# IMX219_Bridge.net
KiCad netlist of a schematic drawn in Altium Designer
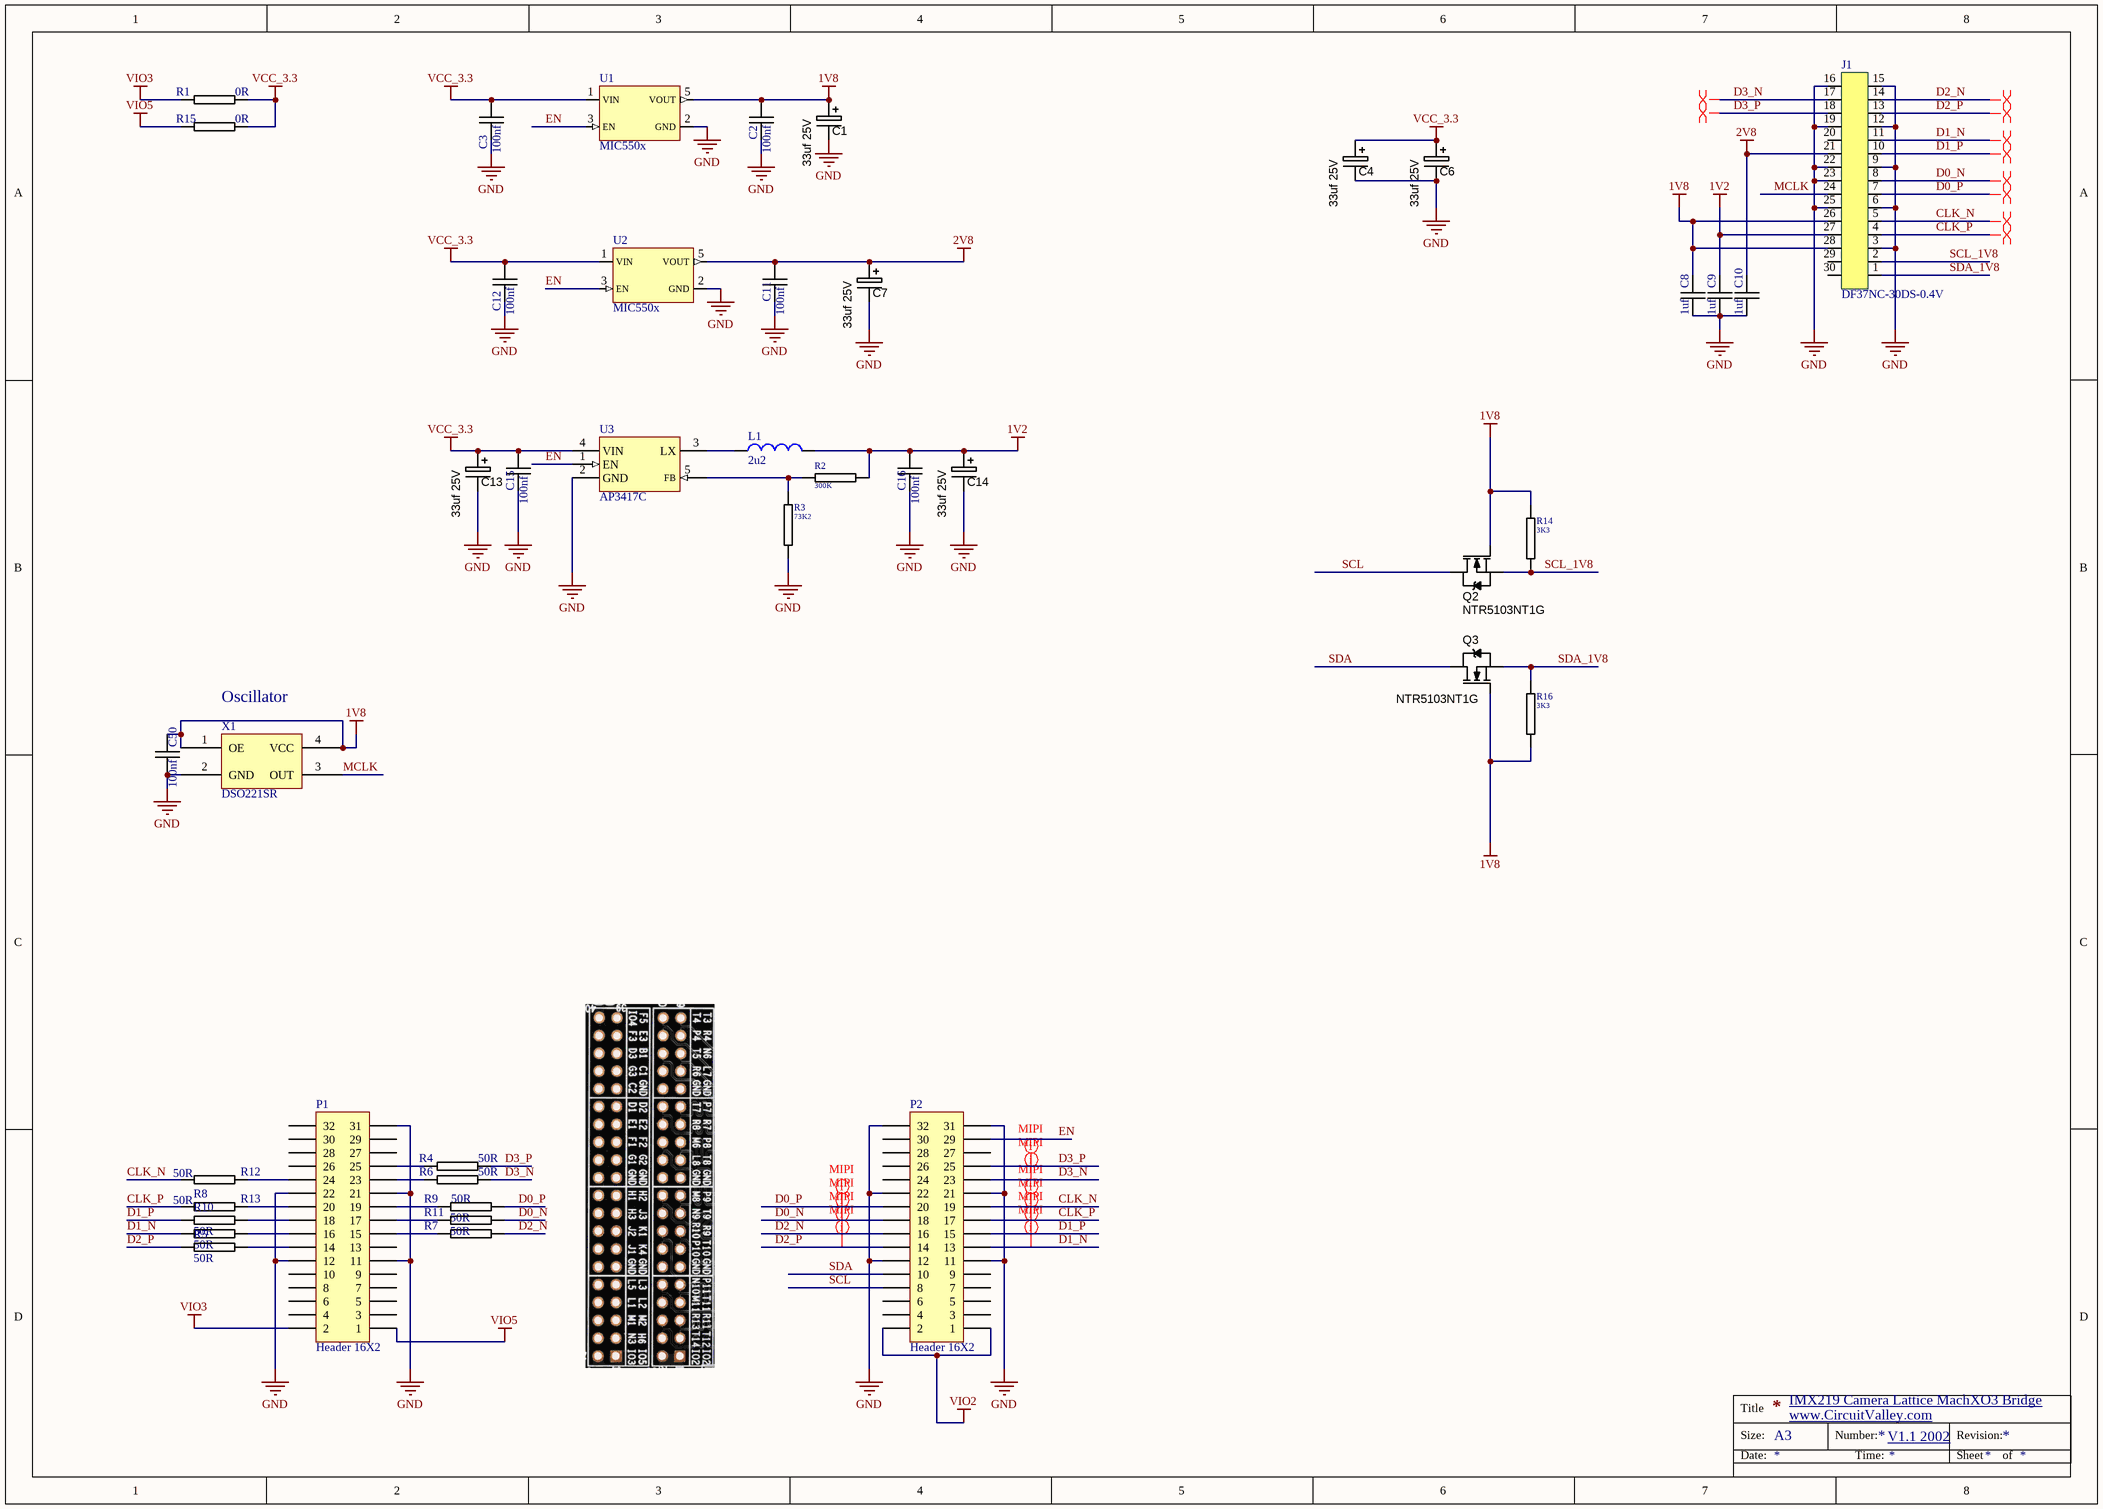
[diagram p0: IMX219_Bridge.SchDoc]

(export (version "E")
  (design (tool "Eeschema 10.0.6"))
  (components
    (comp (ref "C1")
      (value "33uf 25V")
      (footprint "CAPMP7343X310N")
      (description "Capacitor SMD Tant 330uF 20% 6V3 2917")
      (fields
        (field (name "TOLERANCE") "±20%")
        (field (name "MANUFACTURER PART NUMBER") "T520D337M006ATE015")
      )
      (libsource (lib "PBL - Capacitors") (part "CAPT_330u_2917_6V3"))
    )
    (comp (ref "C2")
      (value "100nf")
      (footprint "0603C-GENERIC")
      (description "CAPACITOR 0603 CERAMIC")
      (fields
        (field (name "MANUFACTURER") "Murata Electronics North America")
        (field (name "MANUFACTURER PART NUMBER") "GRM188R60J106ME47D")
      )
      (libsource (lib "Generic") (part "0603C-10UF-6V3-X5R-MUR"))
    )
    (comp (ref "C3")
      (value "100nf")
      (footprint "0603C-GENERIC")
      (description "CAPACITOR 0603 CERAMIC")
      (fields
        (field (name "MANUFACTURER") "Murata Electronics North America")
        (field (name "MANUFACTURER PART NUMBER") "GRM188R60J106ME47D")
      )
      (libsource (lib "Generic") (part "0603C-10UF-6V3-X5R-MUR"))
    )
    (comp (ref "C4")
      (value "33uf 25V")
      (footprint "CAPMP7343X310N")
      (description "Capacitor SMD Tant 330uF 20% 6V3 2917")
      (fields
        (field (name "TOLERANCE") "±20%")
        (field (name "MANUFACTURER PART NUMBER") "T520D337M006ATE015")
      )
      (libsource (lib "PBL - Capacitors") (part "CAPT_330u_2917_6V3"))
    )
    (comp (ref "C6")
      (value "33uf 25V")
      (footprint "CAPMP7343X310N")
      (description "Capacitor SMD Tant 330uF 20% 6V3 2917")
      (fields
        (field (name "TOLERANCE") "±20%")
        (field (name "MANUFACTURER PART NUMBER") "T520D337M006ATE015")
      )
      (libsource (lib "PBL - Capacitors") (part "CAPT_330u_2917_6V3"))
    )
    (comp (ref "C7")
      (value "33uf 25V")
      (footprint "CAPMP7343X310N")
      (description "Capacitor SMD Tant 330uF 20% 6V3 2917")
      (fields
        (field (name "TOLERANCE") "±20%")
        (field (name "MANUFACTURER PART NUMBER") "T520D337M006ATE015")
      )
      (libsource (lib "PBL - Capacitors") (part "CAPT_330u_2917_6V3"))
    )
    (comp (ref "C8")
      (value "1uf")
      (footprint "0805C-TBD")
      (description "CAPACITOR 0805 CERAMIC VALUE TO BE DETERMINED")
      (libsource (lib "Generic") (part "0805C-TBD"))
    )
    (comp (ref "C9")
      (value "1uf")
      (footprint "0805C-TBD")
      (description "CAPACITOR 0805 CERAMIC VALUE TO BE DETERMINED")
      (libsource (lib "Generic") (part "0805C-TBD"))
    )
    (comp (ref "C10")
      (value "1uf")
      (footprint "0805C-TBD")
      (description "CAPACITOR 0805 CERAMIC VALUE TO BE DETERMINED")
      (libsource (lib "Generic") (part "0805C-TBD"))
    )
    (comp (ref "C11")
      (value "100nf")
      (footprint "0603C-GENERIC")
      (description "CAPACITOR 0603 CERAMIC")
      (fields
        (field (name "MANUFACTURER") "Murata Electronics North America")
        (field (name "MANUFACTURER PART NUMBER") "GRM188R60J106ME47D")
      )
      (libsource (lib "Generic") (part "0603C-10UF-6V3-X5R-MUR"))
    )
    (comp (ref "C12")
      (value "100nf")
      (footprint "0603C-GENERIC")
      (description "CAPACITOR 0603 CERAMIC")
      (fields
        (field (name "MANUFACTURER") "Murata Electronics North America")
        (field (name "MANUFACTURER PART NUMBER") "GRM188R60J106ME47D")
      )
      (libsource (lib "Generic") (part "0603C-10UF-6V3-X5R-MUR"))
    )
    (comp (ref "C13")
      (value "33uf 25V")
      (footprint "CAPMP7343X310N")
      (description "Capacitor SMD Tant 330uF 20% 6V3 2917")
      (fields
        (field (name "TOLERANCE") "±20%")
        (field (name "MANUFACTURER PART NUMBER") "T520D337M006ATE015")
      )
      (libsource (lib "PBL - Capacitors") (part "CAPT_330u_2917_6V3"))
    )
    (comp (ref "C14")
      (value "33uf 25V")
      (footprint "CAPMP7343X310N")
      (description "Capacitor SMD Tant 330uF 20% 6V3 2917")
      (fields
        (field (name "TOLERANCE") "±20%")
        (field (name "MANUFACTURER PART NUMBER") "T520D337M006ATE015")
      )
      (libsource (lib "PBL - Capacitors") (part "CAPT_330u_2917_6V3"))
    )
    (comp (ref "C15")
      (value "100nf")
      (footprint "0603C-GENERIC")
      (description "CAPACITOR 0603 CERAMIC")
      (fields
        (field (name "MANUFACTURER") "Murata Electronics North America")
        (field (name "MANUFACTURER PART NUMBER") "GRM188R60J106ME47D")
      )
      (libsource (lib "Generic") (part "0603C-10UF-6V3-X5R-MUR"))
    )
    (comp (ref "C16")
      (value "100nf")
      (footprint "0603C-GENERIC")
      (description "CAPACITOR 0603 CERAMIC")
      (fields
        (field (name "MANUFACTURER") "Murata Electronics North America")
        (field (name "MANUFACTURER PART NUMBER") "GRM188R60J106ME47D")
      )
      (libsource (lib "Generic") (part "0603C-10UF-6V3-X5R-MUR"))
    )
    (comp (ref "C50")
      (value "100nf")
      (footprint "0603C-GENERIC")
      (description "CAPACITOR 0603 CERAMIC")
      (fields
        (field (name "MANUFACTURER") "Murata Electronics North America")
        (field (name "MANUFACTURER PART NUMBER") "GRM188R60J106ME47D")
      )
      (libsource (lib "Generic") (part "0603C-10UF-6V3-X5R-MUR"))
    )
    (comp (ref "J1")
      (value "DF37NC-30DS-0.4V")
      (footprint "DF37NC-30DS-0.4V")
      (libsource (lib "Hiros") (part "30_Pin_Dual"))
    )
    (comp (ref "L1")
      (value "2u2")
      (footprint "TAIYO_NRS4018T2R2MDGJ")
      (fields (field (name "PARTNUMBER") "NRS4018T2R2MDGJ"))
      (libsource (lib "Inductor") (part "inductor_smd"))
    )
    (comp (ref "P1")
      (value "Header 16X2")
      (footprint "HDR2X16")
      (description "Header, 16-Pin, Dual row")
      (fields (field (name "PUBLISHER") "Altium Limited"))
      (libsource (lib "Miscellaneous Connectors") (part "Header 16X2"))
    )
    (comp (ref "P2")
      (value "Header 16X2")
      (footprint "HDR2X16")
      (description "Header, 16-Pin, Dual row")
      (fields (field (name "PUBLISHER") "Altium Limited"))
      (libsource (lib "Miscellaneous Connectors") (part "Header 16X2"))
    )
    (comp (ref "Q2")
      (value "NTR5103NT1G")
      (footprint "SOT23-3")
      (description "MOSFET SMD N-CH 100V 170mA SOT23-3")
      (libsource (lib "PBL - Transistors") (part "MOSFET_BSS123"))
    )
    (comp (ref "Q3")
      (value "NTR5103NT1G")
      (footprint "SOT23-3")
      (description "MOSFET SMD N-CH 100V 170mA SOT23-3")
      (libsource (lib "PBL - Transistors") (part "MOSFET_BSS123"))
    )
    (comp (ref "R1")
      (value "0R")
      (footprint "0805R-0R1")
      (description "RESISTOR 0805 1 WATT")
      (fields
        (field (name "MANUFACTURER PART NUMBER") "RL1220S-R10-F")
        (field (name "MANUFACTURER") "Susumu")
      )
      (libsource (lib "Generic") (part "0805R-0R1"))
    )
    (comp (ref "R2")
      (value "300K")
      (footprint "0603R-10K")
      (description "GENERIC RESISTOR 0603")
      (fields (field (name "MANUFACTURER") "Stackpole Electronics Inc") (field (name "TOLERANCE") "±1%"))
      (libsource (lib "Generic") (part "0603R-10K"))
    )
    (comp (ref "R3")
      (value "73K2")
      (footprint "0603R-10K")
      (description "GENERIC RESISTOR 0603")
      (fields (field (name "MANUFACTURER") "Stackpole Electronics Inc") (field (name "TOLERANCE") "±1%"))
      (libsource (lib "Generic") (part "0603R-10K"))
    )
    (comp (ref "R4")
      (value "50R")
      (footprint "0805R-0R1")
      (description "RESISTOR 0805 1 WATT")
      (fields
        (field (name "MANUFACTURER PART NUMBER") "RL1220S-R10-F")
        (field (name "MANUFACTURER") "Susumu")
      )
      (libsource (lib "Generic") (part "0805R-0R1"))
    )
    (comp (ref "R5")
      (value "50R")
      (footprint "0805R-0R1")
      (description "RESISTOR 0805 1 WATT")
      (fields
        (field (name "MANUFACTURER PART NUMBER") "RL1220S-R10-F")
        (field (name "MANUFACTURER") "Susumu")
      )
      (libsource (lib "Generic") (part "0805R-0R1"))
    )
    (comp (ref "R6")
      (value "50R")
      (footprint "0805R-0R1")
      (description "RESISTOR 0805 1 WATT")
      (fields
        (field (name "MANUFACTURER PART NUMBER") "RL1220S-R10-F")
        (field (name "MANUFACTURER") "Susumu")
      )
      (libsource (lib "Generic") (part "0805R-0R1"))
    )
    (comp (ref "R7")
      (value "50R")
      (footprint "0805R-0R1")
      (description "RESISTOR 0805 1 WATT")
      (fields
        (field (name "MANUFACTURER PART NUMBER") "RL1220S-R10-F")
        (field (name "MANUFACTURER") "Susumu")
      )
      (libsource (lib "Generic") (part "0805R-0R1"))
    )
    (comp (ref "R8")
      (value "50R")
      (footprint "0805R-0R1")
      (description "RESISTOR 0805 1 WATT")
      (fields
        (field (name "MANUFACTURER PART NUMBER") "RL1220S-R10-F")
        (field (name "MANUFACTURER") "Susumu")
      )
      (libsource (lib "Generic") (part "0805R-0R1"))
    )
    (comp (ref "R9")
      (value "50R")
      (footprint "0805R-0R1")
      (description "RESISTOR 0805 1 WATT")
      (fields
        (field (name "MANUFACTURER PART NUMBER") "RL1220S-R10-F")
        (field (name "MANUFACTURER") "Susumu")
      )
      (libsource (lib "Generic") (part "0805R-0R1"))
    )
    (comp (ref "R10")
      (value "50R")
      (footprint "0805R-0R1")
      (description "RESISTOR 0805 1 WATT")
      (fields
        (field (name "MANUFACTURER PART NUMBER") "RL1220S-R10-F")
        (field (name "MANUFACTURER") "Susumu")
      )
      (libsource (lib "Generic") (part "0805R-0R1"))
    )
    (comp (ref "R11")
      (value "50R")
      (footprint "0805R-0R1")
      (description "RESISTOR 0805 1 WATT")
      (fields
        (field (name "MANUFACTURER PART NUMBER") "RL1220S-R10-F")
        (field (name "MANUFACTURER") "Susumu")
      )
      (libsource (lib "Generic") (part "0805R-0R1"))
    )
    (comp (ref "R12")
      (value "50R")
      (footprint "0805R-0R1")
      (description "RESISTOR 0805 1 WATT")
      (fields
        (field (name "MANUFACTURER PART NUMBER") "RL1220S-R10-F")
        (field (name "MANUFACTURER") "Susumu")
      )
      (libsource (lib "Generic") (part "0805R-0R1"))
    )
    (comp (ref "R13")
      (value "50R")
      (footprint "0805R-0R1")
      (description "RESISTOR 0805 1 WATT")
      (fields
        (field (name "MANUFACTURER PART NUMBER") "RL1220S-R10-F")
        (field (name "MANUFACTURER") "Susumu")
      )
      (libsource (lib "Generic") (part "0805R-0R1"))
    )
    (comp (ref "R14")
      (value "3K3")
      (footprint "0603R-10K")
      (description "GENERIC RESISTOR 0603")
      (fields (field (name "MANUFACTURER") "Stackpole Electronics Inc") (field (name "TOLERANCE") "±1%"))
      (libsource (lib "Generic") (part "0603R-10K"))
    )
    (comp (ref "R15")
      (value "0R")
      (footprint "0805R-0R1")
      (description "RESISTOR 0805 1 WATT")
      (fields
        (field (name "MANUFACTURER PART NUMBER") "RL1220S-R10-F")
        (field (name "MANUFACTURER") "Susumu")
      )
      (libsource (lib "Generic") (part "0805R-0R1"))
    )
    (comp (ref "R16")
      (value "3K3")
      (footprint "0603R-10K")
      (description "GENERIC RESISTOR 0603")
      (fields (field (name "MANUFACTURER") "Stackpole Electronics Inc") (field (name "TOLERANCE") "±1%"))
      (libsource (lib "Generic") (part "0603R-10K"))
    )
    (comp (ref "U1") (value "MIC550x") (footprint "SOT23-5") (libsource (lib "cvlib") (part "MIC550x")))
    (comp (ref "U2") (value "MIC550x") (footprint "SOT23-5") (libsource (lib "cvlib") (part "MIC550x")))
    (comp (ref "U3") (value "AP3417C") (footprint "SOT23-5") (libsource (lib "cvlib") (part "AP3417C")))
    (comp (ref "X1")
      (value "DSO221SR")
      (footprint "Active Oscillator 2520")
      (description "Active Oscillator_2520")
      (libsource (lib "Crystal_and_oscillator") (part "Oscillator_2520"))
    )
  )
  (nets
    (net (code "1") (name "/CLK_N") (class "Default")
      (node (ref "J1") (pin "5") (pinfunction "5_5") (pintype "passive"))
      (node (ref "P2") (pin "19") (pinfunction "19_19") (pintype "passive"))
      (node (ref "R12") (pin "2") (pintype "passive"))
    )
    (net (code "2") (name "/CLK_P") (class "Default")
      (node (ref "J1") (pin "4") (pinfunction "4_4") (pintype "passive"))
      (node (ref "P2") (pin "17") (pinfunction "17_17") (pintype "passive"))
      (node (ref "R13") (pin "2") (pintype "passive"))
    )
    (net (code "3") (name "/D0_N") (class "Default")
      (node (ref "J1") (pin "8") (pinfunction "8_8") (pintype "passive"))
      (node (ref "P2") (pin "18") (pinfunction "18_18") (pintype "passive"))
      (node (ref "R11") (pin "2") (pintype "passive"))
    )
    (net (code "4") (name "/D0_P") (class "Default")
      (node (ref "J1") (pin "7") (pinfunction "7_7") (pintype "passive"))
      (node (ref "P2") (pin "20") (pinfunction "20_20") (pintype "passive"))
      (node (ref "R9") (pin "2") (pintype "passive"))
    )
    (net (code "5") (name "/D1_N") (class "Default")
      (node (ref "J1") (pin "11") (pinfunction "11_11") (pintype "passive"))
      (node (ref "P2") (pin "13") (pinfunction "13_13") (pintype "passive"))
      (node (ref "R10") (pin "2") (pintype "passive"))
    )
    (net (code "6") (name "/D1_P") (class "Default")
      (node (ref "J1") (pin "10") (pinfunction "10_10") (pintype "passive"))
      (node (ref "P2") (pin "15") (pinfunction "15_15") (pintype "passive"))
      (node (ref "R8") (pin "2") (pintype "passive"))
    )
    (net (code "7") (name "/D2_N") (class "Default")
      (node (ref "J1") (pin "14") (pinfunction "14_14") (pintype "passive"))
      (node (ref "P2") (pin "16") (pinfunction "16_16") (pintype "passive"))
      (node (ref "R7") (pin "1") (pintype "passive"))
    )
    (net (code "8") (name "/D2_P") (class "Default")
      (node (ref "J1") (pin "13") (pinfunction "13_13") (pintype "passive"))
      (node (ref "P2") (pin "14") (pinfunction "14_14") (pintype "passive"))
      (node (ref "R5") (pin "2") (pintype "passive"))
    )
    (net (code "9") (name "/D3_N") (class "Default")
      (node (ref "J1") (pin "17") (pinfunction "17_17") (pintype "passive"))
      (node (ref "P2") (pin "23") (pinfunction "23_23") (pintype "passive"))
      (node (ref "R6") (pin "2") (pintype "passive"))
    )
    (net (code "10") (name "/D3_P") (class "Default")
      (node (ref "J1") (pin "18") (pinfunction "18_18") (pintype "passive"))
      (node (ref "P2") (pin "25") (pinfunction "25_25") (pintype "passive"))
      (node (ref "R4") (pin "2") (pintype "passive"))
    )
    (net (code "11") (name "/EN") (class "Default")
      (node (ref "P2") (pin "29") (pinfunction "29_29") (pintype "passive"))
      (node (ref "U1") (pin "3") (pinfunction "EN_3") (pintype "input"))
      (node (ref "U2") (pin "3") (pinfunction "EN_3") (pintype "input"))
      (node (ref "U3") (pin "1") (pinfunction "EN_1") (pintype "input"))
    )
    (net (code "12") (name "/MCLK") (class "Default")
      (node (ref "J1") (pin "24") (pinfunction "24_24") (pintype "passive"))
      (node (ref "X1") (pin "3") (pinfunction "OUT_3") (pintype "passive"))
    )
    (net (code "13") (name "/SCL") (class "Default")
      (node (ref "P2") (pin "8") (pinfunction "8_8") (pintype "passive"))
      (node (ref "Q2") (pin "3") (pinfunction "D_3") (pintype "passive"))
    )
    (net (code "14") (name "/SCL_1V8") (class "Default")
      (node (ref "J1") (pin "2") (pinfunction "2_2") (pintype "passive"))
      (node (ref "Q2") (pin "2") (pinfunction "S_2") (pintype "passive"))
      (node (ref "R14") (pin "1") (pintype "passive"))
    )
    (net (code "15") (name "/SDA") (class "Default")
      (node (ref "P2") (pin "10") (pinfunction "10_10") (pintype "passive"))
      (node (ref "Q3") (pin "3") (pinfunction "D_3") (pintype "passive"))
    )
    (net (code "16") (name "/SDA_1V8") (class "Default")
      (node (ref "J1") (pin "1") (pinfunction "1_1") (pintype "passive"))
      (node (ref "Q3") (pin "2") (pinfunction "S_2") (pintype "passive"))
      (node (ref "R16") (pin "2") (pintype "passive"))
    )
    (net (code "17") (name "1V2") (class "Default")
      (node (ref "C14") (pin "1") (pintype "passive"))
      (node (ref "C16") (pin "2") (pintype "passive"))
      (node (ref "C9") (pin "1") (pintype "passive"))
      (node (ref "J1") (pin "27") (pinfunction "27_27") (pintype "passive"))
      (node (ref "L1") (pin "2") (pinfunction "2_2") (pintype "passive"))
      (node (ref "R2") (pin "2") (pintype "passive"))
    )
    (net (code "18") (name "1V8") (class "Default")
      (node (ref "C1") (pin "1") (pintype "passive"))
      (node (ref "C2") (pin "2") (pintype "passive"))
      (node (ref "C50") (pin "2") (pintype "passive"))
      (node (ref "C8") (pin "1") (pintype "passive"))
      (node (ref "J1") (pin "26") (pinfunction "26_26") (pintype "passive"))
      (node (ref "J1") (pin "28") (pinfunction "28_28") (pintype "passive"))
      (node (ref "Q2") (pin "1") (pinfunction "G_1") (pintype "passive"))
      (node (ref "Q3") (pin "1") (pinfunction "G_1") (pintype "passive"))
      (node (ref "R14") (pin "2") (pintype "passive"))
      (node (ref "R16") (pin "1") (pintype "passive"))
      (node (ref "U1") (pin "5") (pinfunction "VOUT_5") (pintype "output"))
      (node (ref "X1") (pin "1") (pinfunction "OE_1") (pintype "passive"))
      (node (ref "X1") (pin "4") (pinfunction "VCC_4") (pintype "passive"))
    )
    (net (code "19") (name "2V8") (class "Default")
      (node (ref "C10") (pin "1") (pintype "passive"))
      (node (ref "C11") (pin "2") (pintype "passive"))
      (node (ref "C7") (pin "1") (pintype "passive"))
      (node (ref "J1") (pin "21") (pinfunction "21_21") (pintype "passive"))
      (node (ref "U2") (pin "5") (pinfunction "VOUT_5") (pintype "output"))
    )
    (net (code "20") (name "GND") (class "Default")
      (node (ref "C1") (pin "2") (pintype "passive"))
      (node (ref "C10") (pin "2") (pintype "passive"))
      (node (ref "C11") (pin "1") (pintype "passive"))
      (node (ref "C12") (pin "1") (pintype "passive"))
      (node (ref "C13") (pin "2") (pintype "passive"))
      (node (ref "C14") (pin "2") (pintype "passive"))
      (node (ref "C15") (pin "1") (pintype "passive"))
      (node (ref "C16") (pin "1") (pintype "passive"))
      (node (ref "C2") (pin "1") (pintype "passive"))
      (node (ref "C3") (pin "1") (pintype "passive"))
      (node (ref "C4") (pin "2") (pintype "passive"))
      (node (ref "C50") (pin "1") (pintype "passive"))
      (node (ref "C6") (pin "2") (pintype "passive"))
      (node (ref "C7") (pin "2") (pintype "passive"))
      (node (ref "C8") (pin "2") (pintype "passive"))
      (node (ref "C9") (pin "2") (pintype "passive"))
      (node (ref "J1") (pin "12") (pinfunction "12_12") (pintype "passive"))
      (node (ref "J1") (pin "15") (pinfunction "15_15") (pintype "passive"))
      (node (ref "J1") (pin "16") (pinfunction "16_16") (pintype "passive"))
      (node (ref "J1") (pin "19") (pinfunction "19_19") (pintype "passive"))
      (node (ref "J1") (pin "22") (pinfunction "22_22") (pintype "passive"))
      (node (ref "J1") (pin "23") (pinfunction "23_23") (pintype "passive"))
      (node (ref "J1") (pin "25") (pinfunction "25_25") (pintype "passive"))
      (node (ref "J1") (pin "3") (pinfunction "3_3") (pintype "passive"))
      (node (ref "J1") (pin "6") (pinfunction "6_6") (pintype "passive"))
      (node (ref "J1") (pin "9") (pinfunction "9_9") (pintype "passive"))
      (node (ref "P1") (pin "11") (pinfunction "11_11") (pintype "passive"))
      (node (ref "P1") (pin "12") (pinfunction "12_12") (pintype "passive"))
      (node (ref "P1") (pin "21") (pinfunction "21_21") (pintype "passive"))
      (node (ref "P1") (pin "22") (pinfunction "22_22") (pintype "passive"))
      (node (ref "P1") (pin "31") (pinfunction "31_31") (pintype "passive"))
      (node (ref "P2") (pin "11") (pinfunction "11_11") (pintype "passive"))
      (node (ref "P2") (pin "12") (pinfunction "12_12") (pintype "passive"))
      (node (ref "P2") (pin "21") (pinfunction "21_21") (pintype "passive"))
      (node (ref "P2") (pin "22") (pinfunction "22_22") (pintype "passive"))
      (node (ref "P2") (pin "31") (pinfunction "31_31") (pintype "passive"))
      (node (ref "P2") (pin "32") (pinfunction "32_32") (pintype "passive"))
      (node (ref "R3") (pin "1") (pintype "passive"))
      (node (ref "U1") (pin "2") (pinfunction "GND_2") (pintype "power_in"))
      (node (ref "U2") (pin "2") (pinfunction "GND_2") (pintype "power_in"))
      (node (ref "U3") (pin "2") (pinfunction "GND_2") (pintype "power_in"))
      (node (ref "X1") (pin "2") (pinfunction "GND_2") (pintype "passive"))
    )
    (net (code "21") (name "Net-(P1-Pad14)") (class "Default")
      (node (ref "P1") (pin "14") (pinfunction "14_14") (pintype "passive"))
      (node (ref "R5") (pin "1") (pintype "passive"))
    )
    (net (code "22") (name "Net-(P1-Pad15)") (class "Default")
      (node (ref "P1") (pin "15") (pinfunction "15_15") (pintype "passive"))
      (node (ref "R7") (pin "2") (pintype "passive"))
    )
    (net (code "23") (name "Net-(P1-Pad16)") (class "Default")
      (node (ref "P1") (pin "16") (pinfunction "16_16") (pintype "passive"))
      (node (ref "R10") (pin "1") (pintype "passive"))
    )
    (net (code "24") (name "Net-(P1-Pad17)") (class "Default")
      (node (ref "P1") (pin "17") (pinfunction "17_17") (pintype "passive"))
      (node (ref "R11") (pin "1") (pintype "passive"))
    )
    (net (code "25") (name "Net-(P1-Pad18)") (class "Default")
      (node (ref "P1") (pin "18") (pinfunction "18_18") (pintype "passive"))
      (node (ref "R8") (pin "1") (pintype "passive"))
    )
    (net (code "26") (name "Net-(P1-Pad19)") (class "Default")
      (node (ref "P1") (pin "19") (pinfunction "19_19") (pintype "passive"))
      (node (ref "R9") (pin "1") (pintype "passive"))
    )
    (net (code "27") (name "Net-(P1-Pad20)") (class "Default")
      (node (ref "P1") (pin "20") (pinfunction "20_20") (pintype "passive"))
      (node (ref "R13") (pin "1") (pintype "passive"))
    )
    (net (code "28") (name "Net-(P1-Pad23)") (class "Default")
      (node (ref "P1") (pin "23") (pinfunction "23_23") (pintype "passive"))
      (node (ref "R6") (pin "1") (pintype "passive"))
    )
    (net (code "29") (name "Net-(P1-Pad24)") (class "Default")
      (node (ref "P1") (pin "24") (pinfunction "24_24") (pintype "passive"))
      (node (ref "R12") (pin "1") (pintype "passive"))
    )
    (net (code "30") (name "Net-(P1-Pad25)") (class "Default")
      (node (ref "P1") (pin "25") (pinfunction "25_25") (pintype "passive"))
      (node (ref "R4") (pin "1") (pintype "passive"))
    )
    (net (code "31") (name "Net-(U3-FB)") (class "Default")
      (node (ref "R2") (pin "1") (pintype "passive"))
      (node (ref "R3") (pin "2") (pintype "passive"))
      (node (ref "U3") (pin "5") (pinfunction "FB_5") (pintype "input"))
    )
    (net (code "32") (name "Net-(U3-LX)") (class "Default")
      (node (ref "L1") (pin "1") (pinfunction "1_1") (pintype "passive"))
      (node (ref "U3") (pin "3") (pinfunction "LX_3") (pintype "passive"))
    )
    (net (code "33") (name "VCC_3.3") (class "Default")
      (node (ref "C12") (pin "2") (pintype "passive"))
      (node (ref "C13") (pin "1") (pintype "passive"))
      (node (ref "C15") (pin "2") (pintype "passive"))
      (node (ref "C3") (pin "2") (pintype "passive"))
      (node (ref "C4") (pin "1") (pintype "passive"))
      (node (ref "C6") (pin "1") (pintype "passive"))
      (node (ref "R1") (pin "2") (pintype "passive"))
      (node (ref "R15") (pin "2") (pintype "passive"))
      (node (ref "U1") (pin "1") (pinfunction "VIN_1") (pintype "power_in"))
      (node (ref "U2") (pin "1") (pinfunction "VIN_1") (pintype "power_in"))
      (node (ref "U3") (pin "4") (pinfunction "VIN_4") (pintype "power_in"))
    )
    (net (code "34") (name "VIO2") (class "Default")
      (node (ref "P2") (pin "1") (pinfunction "1_1") (pintype "passive"))
      (node (ref "P2") (pin "2") (pinfunction "2_2") (pintype "passive"))
    )
    (net (code "35") (name "VIO3") (class "Default")
      (node (ref "P1") (pin "2") (pinfunction "2_2") (pintype "passive"))
      (node (ref "R1") (pin "1") (pintype "passive"))
    )
    (net (code "36") (name "VIO5") (class "Default")
      (node (ref "P1") (pin "1") (pinfunction "1_1") (pintype "passive"))
      (node (ref "R15") (pin "1") (pintype "passive"))
    )
    (net (code "37") (name "unconnected-(J1-Pad20)") (class "Default")
      (node (ref "J1") (pin "20") (pinfunction "20_20") (pintype "passive"))
    )
    (net (code "38") (name "unconnected-(J1-Pad29)") (class "Default")
      (node (ref "J1") (pin "29") (pinfunction "29_29") (pintype "passive"))
    )
    (net (code "39") (name "unconnected-(J1-Pad30)") (class "Default")
      (node (ref "J1") (pin "30") (pinfunction "30_30") (pintype "passive"))
    )
    (net (code "40") (name "unconnected-(P1-Pad3)") (class "Default")
      (node (ref "P1") (pin "3") (pinfunction "3_3") (pintype "passive"))
    )
    (net (code "41") (name "unconnected-(P1-Pad4)") (class "Default")
      (node (ref "P1") (pin "4") (pinfunction "4_4") (pintype "passive"))
    )
    (net (code "42") (name "unconnected-(P1-Pad5)") (class "Default")
      (node (ref "P1") (pin "5") (pinfunction "5_5") (pintype "passive"))
    )
    (net (code "43") (name "unconnected-(P1-Pad6)") (class "Default")
      (node (ref "P1") (pin "6") (pinfunction "6_6") (pintype "passive"))
    )
    (net (code "44") (name "unconnected-(P1-Pad7)") (class "Default")
      (node (ref "P1") (pin "7") (pinfunction "7_7") (pintype "passive"))
    )
    (net (code "45") (name "unconnected-(P1-Pad8)") (class "Default")
      (node (ref "P1") (pin "8") (pinfunction "8_8") (pintype "passive"))
    )
    (net (code "46") (name "unconnected-(P1-Pad9)") (class "Default")
      (node (ref "P1") (pin "9") (pinfunction "9_9") (pintype "passive"))
    )
    (net (code "47") (name "unconnected-(P1-Pad10)") (class "Default")
      (node (ref "P1") (pin "10") (pinfunction "10_10") (pintype "passive"))
    )
    (net (code "48") (name "unconnected-(P1-Pad13)") (class "Default")
      (node (ref "P1") (pin "13") (pinfunction "13_13") (pintype "passive"))
    )
    (net (code "49") (name "unconnected-(P1-Pad26)") (class "Default")
      (node (ref "P1") (pin "26") (pinfunction "26_26") (pintype "passive"))
    )
    (net (code "50") (name "unconnected-(P1-Pad27)") (class "Default")
      (node (ref "P1") (pin "27") (pinfunction "27_27") (pintype "passive"))
    )
    (net (code "51") (name "unconnected-(P1-Pad28)") (class "Default")
      (node (ref "P1") (pin "28") (pinfunction "28_28") (pintype "passive"))
    )
    (net (code "52") (name "unconnected-(P1-Pad29)") (class "Default")
      (node (ref "P1") (pin "29") (pinfunction "29_29") (pintype "passive"))
    )
    (net (code "53") (name "unconnected-(P1-Pad30)") (class "Default")
      (node (ref "P1") (pin "30") (pinfunction "30_30") (pintype "passive"))
    )
    (net (code "54") (name "unconnected-(P1-Pad32)") (class "Default")
      (node (ref "P1") (pin "32") (pinfunction "32_32") (pintype "passive"))
    )
    (net (code "55") (name "unconnected-(P2-Pad3)") (class "Default")
      (node (ref "P2") (pin "3") (pinfunction "3_3") (pintype "passive"))
    )
    (net (code "56") (name "unconnected-(P2-Pad4)") (class "Default")
      (node (ref "P2") (pin "4") (pinfunction "4_4") (pintype "passive"))
    )
    (net (code "57") (name "unconnected-(P2-Pad5)") (class "Default")
      (node (ref "P2") (pin "5") (pinfunction "5_5") (pintype "passive"))
    )
    (net (code "58") (name "unconnected-(P2-Pad6)") (class "Default")
      (node (ref "P2") (pin "6") (pinfunction "6_6") (pintype "passive"))
    )
    (net (code "59") (name "unconnected-(P2-Pad7)") (class "Default")
      (node (ref "P2") (pin "7") (pinfunction "7_7") (pintype "passive"))
    )
    (net (code "60") (name "unconnected-(P2-Pad9)") (class "Default")
      (node (ref "P2") (pin "9") (pinfunction "9_9") (pintype "passive"))
    )
    (net (code "61") (name "unconnected-(P2-Pad24)") (class "Default")
      (node (ref "P2") (pin "24") (pinfunction "24_24") (pintype "passive"))
    )
    (net (code "62") (name "unconnected-(P2-Pad26)") (class "Default")
      (node (ref "P2") (pin "26") (pinfunction "26_26") (pintype "passive"))
    )
    (net (code "63") (name "unconnected-(P2-Pad27)") (class "Default")
      (node (ref "P2") (pin "27") (pinfunction "27_27") (pintype "passive"))
    )
    (net (code "64") (name "unconnected-(P2-Pad28)") (class "Default")
      (node (ref "P2") (pin "28") (pinfunction "28_28") (pintype "passive"))
    )
    (net (code "65") (name "unconnected-(P2-Pad30)") (class "Default")
      (node (ref "P2") (pin "30") (pinfunction "30_30") (pintype "passive"))
    )
  )
)
